# SparkFun_Gyro_Breakout-L3G4200D.net
KiCad netlist of a schematic drawn in EAGLE
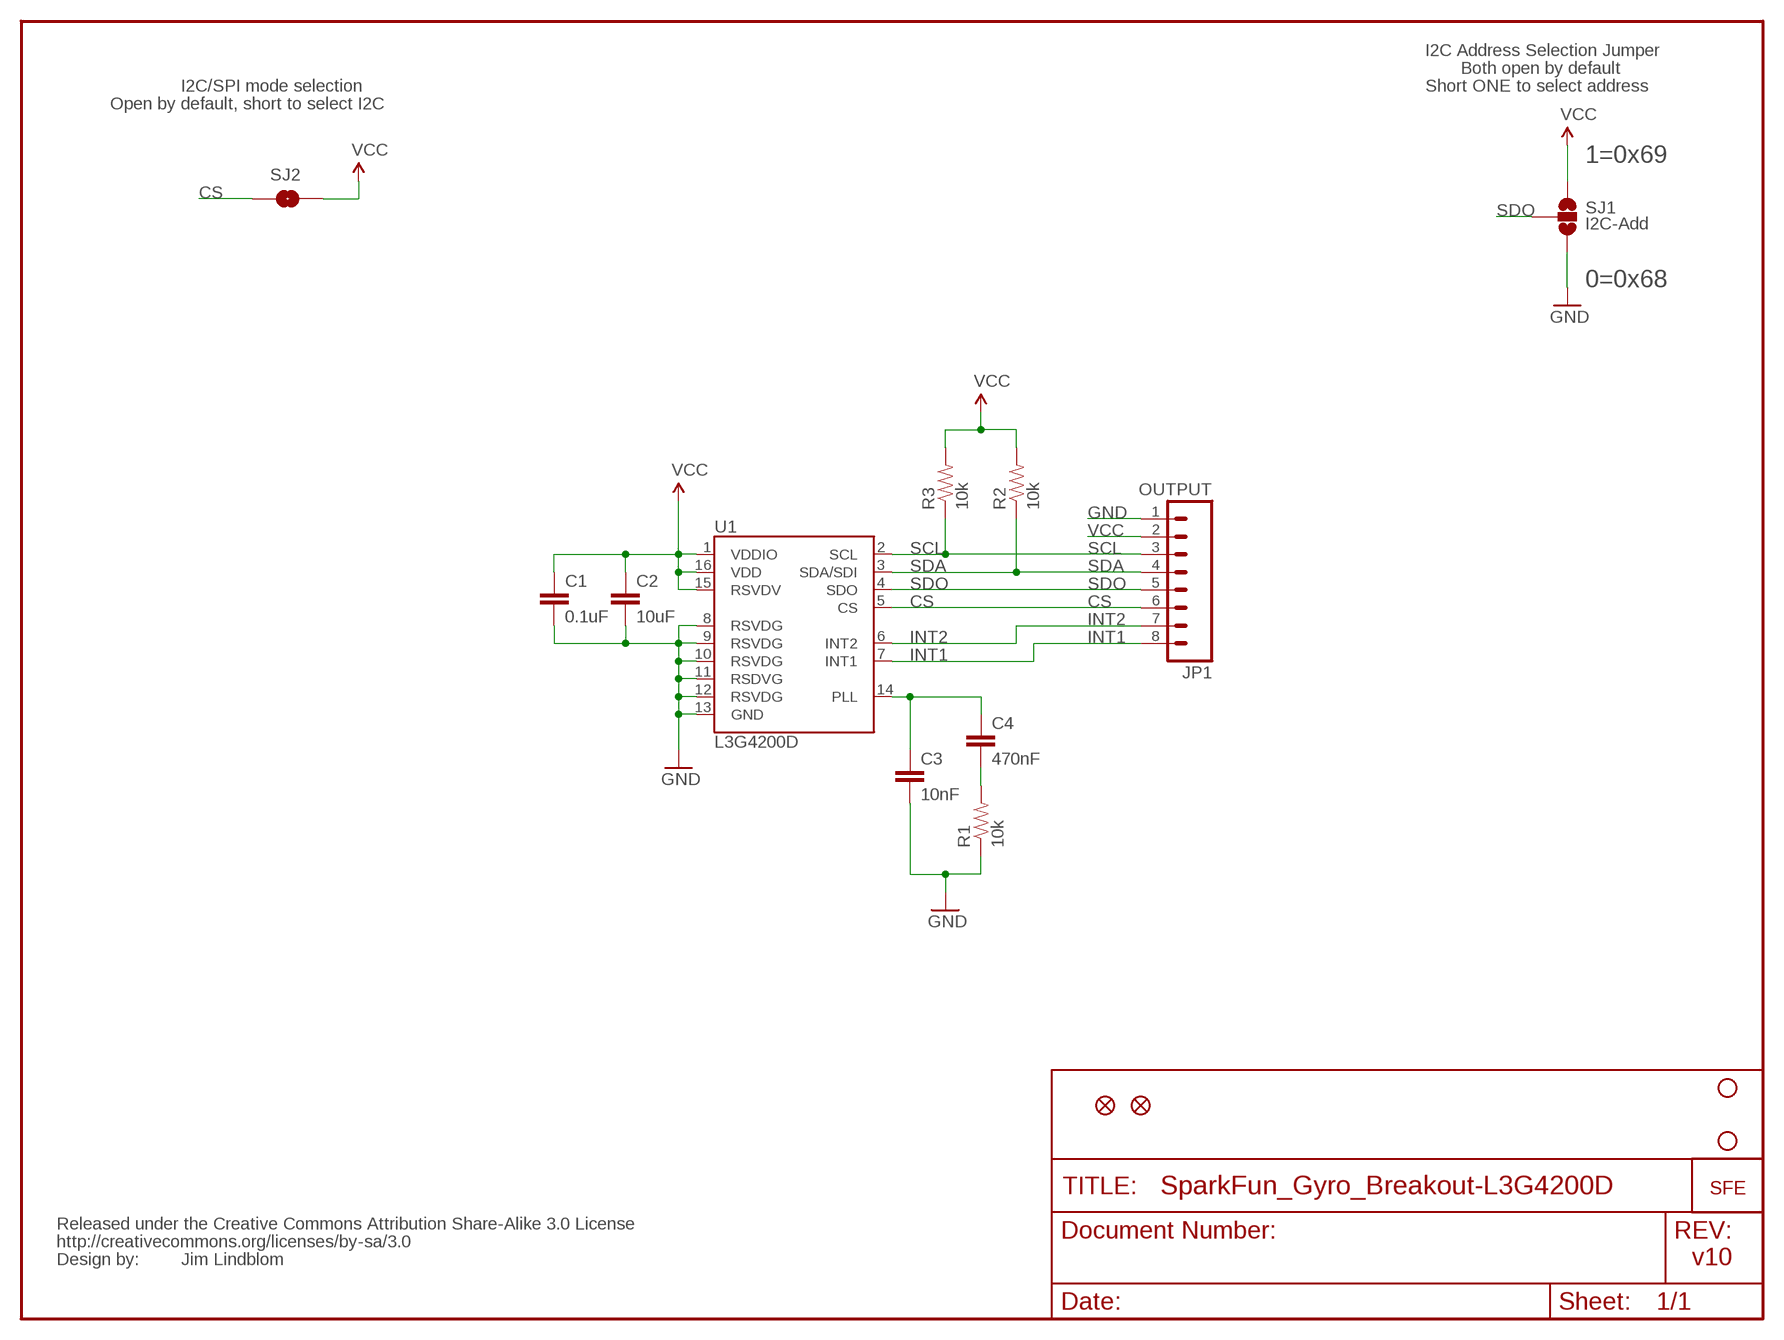
[diagram p0: schematic, sheet 1]

(export (version "E")
  (design (tool "Eeschema 10.0.6"))
  (components
    (comp (ref "C1")
      (value "0.1uF")
      (footprint "eagle-import:0402-CAP")
      (libsource (lib "eagle-import") (part "CAP0402-CAP"))
    )
    (comp (ref "C2")
      (value "10uF")
      (footprint "eagle-import:1206")
      (libsource (lib "eagle-import") (part "CAP1206"))
    )
    (comp (ref "C3")
      (value "10nF")
      (footprint "eagle-import:0402-CAP")
      (libsource (lib "eagle-import") (part "CAP0402-CAP"))
    )
    (comp (ref "C4")
      (value "470nF")
      (footprint "eagle-import:0402-CAP")
      (libsource (lib "eagle-import") (part "CAP0402-CAP"))
    )
    (comp (ref "JP1")
      (value "OUTPUT")
      (footprint "eagle-import:1X08")
      (libsource (lib "eagle-import") (part "M08"))
    )
    (comp (ref "JP2")
      (value "STAND-OFF")
      (footprint "eagle-import:STAND-OFF")
      (libsource (lib "eagle-import") (part "STAND-OFF"))
    )
    (comp (ref "JP3")
      (value "STAND-OFF")
      (footprint "eagle-import:STAND-OFF")
      (libsource (lib "eagle-import") (part "STAND-OFF"))
    )
    (comp (ref "JP4")
      (value "LOGO-SFESK")
      (footprint "eagle-import:SFE-LOGO-FLAME")
      (libsource (lib "eagle-import") (part "LOGO-SFESK"))
    )
    (comp (ref "JP5")
      (value "FIDUCIAL1X2")
      (footprint "eagle-import:FIDUCIAL-1X2")
      (libsource (lib "eagle-import") (part "FIDUCIAL1X2"))
    )
    (comp (ref "JP6")
      (value "FIDUCIAL1X2")
      (footprint "eagle-import:FIDUCIAL-1X2")
      (libsource (lib "eagle-import") (part "FIDUCIAL1X2"))
    )
    (comp (ref "R1")
      (value "10k")
      (footprint "eagle-import:0402-RES")
      (libsource (lib "eagle-import") (part "RESISTOR0402-RES"))
    )
    (comp (ref "R2")
      (value "10k")
      (footprint "eagle-import:0402-RES")
      (libsource (lib "eagle-import") (part "RESISTOR0402-RES"))
    )
    (comp (ref "R3")
      (value "10k")
      (footprint "eagle-import:0402-RES")
      (libsource (lib "eagle-import") (part "RESISTOR0402-RES"))
    )
    (comp (ref "SJ1")
      (value "I2C-Add")
      (footprint "eagle-import:SJ_3")
      (libsource (lib "eagle-import") (part "SOLDERJUMPER_2WAYS"))
    )
    (comp (ref "SJ2")
      (value "I2C-Mode")
      (footprint "eagle-import:SJ_2S-NO")
      (libsource (lib "eagle-import") (part "SOLDERJUMPERNO"))
    )
    (comp (ref "U$1")
      (value "CREATIVE_COMMONS")
      (footprint "eagle-import:CREATIVE_COMMONS")
      (libsource (lib "eagle-import") (part "CREATIVE_COMMONS"))
    )
    (comp (ref "U1")
      (value "L3G4200D")
      (footprint "eagle-import:LGA16-4X4")
      (libsource (lib "eagle-import") (part "L3G4200D"))
    )
  )
  (nets
    (net (code "1") (name "/CS") (class "Default")
      (node (ref "JP1") (pin "6") (pinfunction "6_6") (pintype "passive"))
      (node (ref "SJ2") (pin "1") (pinfunction "1_1") (pintype "passive"))
      (node (ref "U1") (pin "5") (pinfunction "CS_5") (pintype "bidirectional"))
    )
    (net (code "2") (name "/INT1") (class "Default")
      (node (ref "JP1") (pin "8") (pinfunction "8_8") (pintype "passive"))
      (node (ref "U1") (pin "7") (pinfunction "INT1_7") (pintype "bidirectional"))
    )
    (net (code "3") (name "/INT2") (class "Default")
      (node (ref "JP1") (pin "7") (pinfunction "7_7") (pintype "passive"))
      (node (ref "U1") (pin "6") (pinfunction "INT2_6") (pintype "bidirectional"))
    )
    (net (code "4") (name "/SCL") (class "Default")
      (node (ref "JP1") (pin "3") (pinfunction "3_3") (pintype "passive"))
      (node (ref "R3") (pin "1") (pinfunction "1_1") (pintype "passive"))
      (node (ref "U1") (pin "2") (pinfunction "SCL_2") (pintype "bidirectional"))
    )
    (net (code "5") (name "/SDA") (class "Default")
      (node (ref "JP1") (pin "4") (pinfunction "4_4") (pintype "passive"))
      (node (ref "R2") (pin "1") (pinfunction "1_1") (pintype "passive"))
      (node (ref "U1") (pin "3") (pinfunction "SDA/SDI_3") (pintype "bidirectional"))
    )
    (net (code "6") (name "/SDO") (class "Default")
      (node (ref "JP1") (pin "5") (pinfunction "5_5") (pintype "passive"))
      (node (ref "SJ1") (pin "2") (pinfunction "2_2") (pintype "passive"))
      (node (ref "U1") (pin "4") (pinfunction "SDO_4") (pintype "bidirectional"))
    )
    (net (code "7") (name "GND") (class "Default")
      (node (ref "C1") (pin "2") (pinfunction "2_2") (pintype "passive"))
      (node (ref "C2") (pin "2") (pinfunction "2_2") (pintype "passive"))
      (node (ref "C3") (pin "2") (pinfunction "2_2") (pintype "passive"))
      (node (ref "JP1") (pin "1") (pinfunction "1_1") (pintype "passive"))
      (node (ref "R1") (pin "1") (pinfunction "1_1") (pintype "passive"))
      (node (ref "SJ1") (pin "3") (pinfunction "3_3") (pintype "passive"))
      (node (ref "U1") (pin "10") (pinfunction "RSVDG_10") (pintype "bidirectional"))
      (node (ref "U1") (pin "11") (pinfunction "RSDVG_11") (pintype "bidirectional"))
      (node (ref "U1") (pin "12") (pinfunction "RSVDG_12") (pintype "bidirectional"))
      (node (ref "U1") (pin "13") (pinfunction "GND_13") (pintype "bidirectional"))
      (node (ref "U1") (pin "8") (pinfunction "RSVDG_8") (pintype "bidirectional"))
      (node (ref "U1") (pin "9") (pinfunction "RSVDG_9") (pintype "bidirectional"))
    )
    (net (code "8") (name "Net-(C4-Pad2)") (class "Default")
      (node (ref "C4") (pin "2") (pinfunction "2_2") (pintype "passive"))
      (node (ref "R1") (pin "2") (pinfunction "2_2") (pintype "passive"))
    )
    (net (code "9") (name "Net-(U1-PLL)") (class "Default")
      (node (ref "C3") (pin "1") (pinfunction "1_1") (pintype "passive"))
      (node (ref "C4") (pin "1") (pinfunction "1_1") (pintype "passive"))
      (node (ref "U1") (pin "14") (pinfunction "PLL_14") (pintype "bidirectional"))
    )
    (net (code "10") (name "VCC") (class "Default")
      (node (ref "C1") (pin "1") (pinfunction "1_1") (pintype "passive"))
      (node (ref "C2") (pin "1") (pinfunction "1_1") (pintype "passive"))
      (node (ref "JP1") (pin "2") (pinfunction "2_2") (pintype "passive"))
      (node (ref "R2") (pin "2") (pinfunction "2_2") (pintype "passive"))
      (node (ref "R3") (pin "2") (pinfunction "2_2") (pintype "passive"))
      (node (ref "SJ1") (pin "1") (pinfunction "1_1") (pintype "passive"))
      (node (ref "SJ2") (pin "2") (pinfunction "2_2") (pintype "passive"))
      (node (ref "U1") (pin "1") (pinfunction "VDDIO_1") (pintype "bidirectional"))
      (node (ref "U1") (pin "15") (pinfunction "RSVDV_15") (pintype "bidirectional"))
      (node (ref "U1") (pin "16") (pinfunction "VDD_16") (pintype "bidirectional"))
    )
  )
)
